# Connector_Board.net
KiCad netlist of a schematic drawn in EAGLE
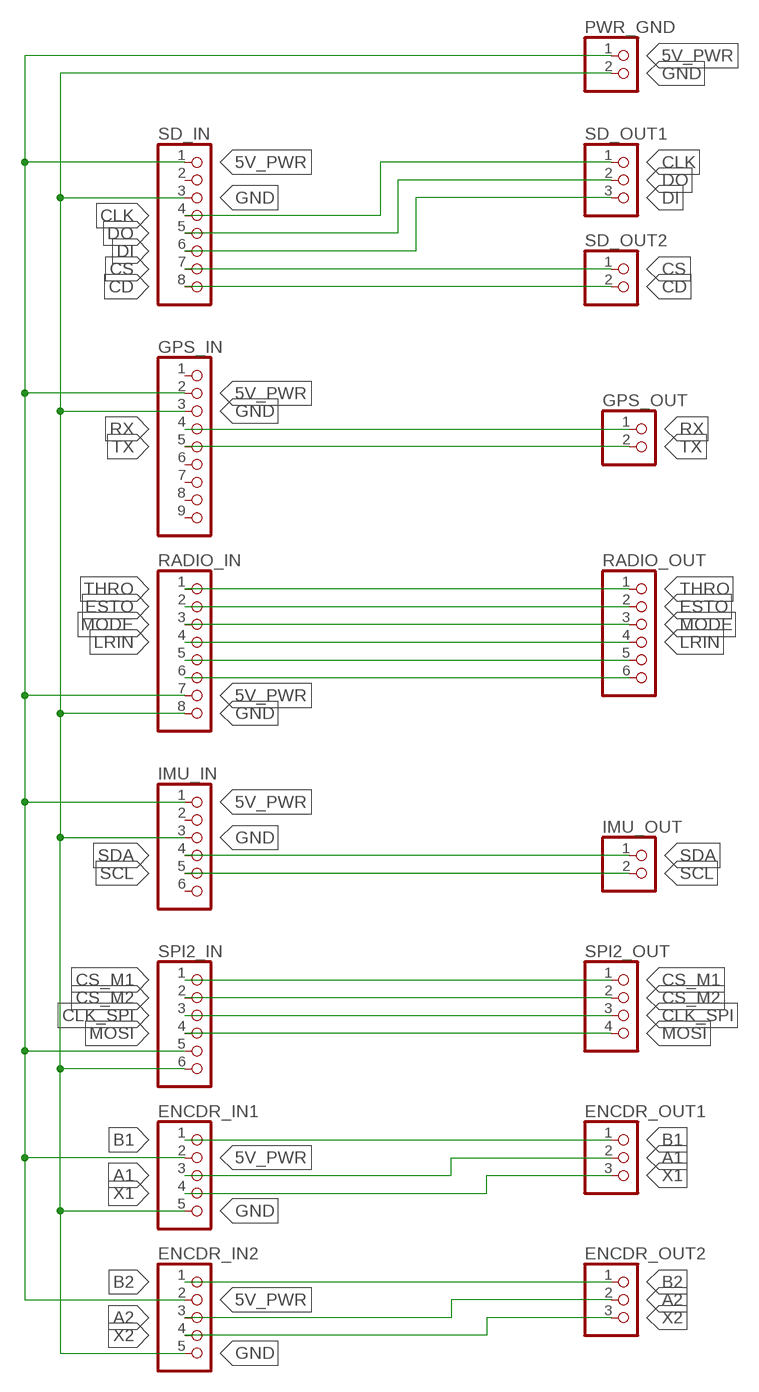
[diagram p0: schematic, sheet 1]

(export (version "E")
  (design (tool "Eeschema 10.0.6"))
  (components
    (comp (ref "ENCDR_IN1")
      (value "PINHD-1X5")
      (footprint "eagle-import:1X05")
      (libsource (lib "eagle-import") (part "PINHD-1X5"))
    )
    (comp (ref "ENCDR_IN2")
      (value "PINHD-1X5")
      (footprint "eagle-import:1X05")
      (libsource (lib "eagle-import") (part "PINHD-1X5"))
    )
    (comp (ref "ENCDR_OUT1")
      (value "PINHD-1X3")
      (footprint "eagle-import:1X03")
      (libsource (lib "eagle-import") (part "PINHD-1X3"))
    )
    (comp (ref "ENCDR_OUT2")
      (value "PINHD-1X3")
      (footprint "eagle-import:1X03")
      (libsource (lib "eagle-import") (part "PINHD-1X3"))
    )
    (comp (ref "GPS_IN")
      (value "PINHD-1X9")
      (footprint "eagle-import:1X09")
      (libsource (lib "eagle-import") (part "PINHD-1X9"))
    )
    (comp (ref "GPS_OUT")
      (value "PINHD-1X2")
      (footprint "eagle-import:1X02")
      (libsource (lib "eagle-import") (part "PINHD-1X2"))
    )
    (comp (ref "IMU_IN")
      (value "PINHD-1X6")
      (footprint "eagle-import:1X06")
      (libsource (lib "eagle-import") (part "PINHD-1X6"))
    )
    (comp (ref "IMU_OUT")
      (value "PINHD-1X2")
      (footprint "eagle-import:1X02")
      (libsource (lib "eagle-import") (part "PINHD-1X2"))
    )
    (comp (ref "PWR_GND")
      (value "PINHD-1X2")
      (footprint "eagle-import:1X02")
      (libsource (lib "eagle-import") (part "PINHD-1X2"))
    )
    (comp (ref "RADIO_IN")
      (value "PINHD-1X8")
      (footprint "eagle-import:1X08")
      (libsource (lib "eagle-import") (part "PINHD-1X8"))
    )
    (comp (ref "RADIO_OUT")
      (value "PINHD-1X6")
      (footprint "eagle-import:1X06")
      (libsource (lib "eagle-import") (part "PINHD-1X6"))
    )
    (comp (ref "SD_IN")
      (value "PINHD-1X8")
      (footprint "eagle-import:1X08")
      (libsource (lib "eagle-import") (part "PINHD-1X8"))
    )
    (comp (ref "SD_OUT1")
      (value "PINHD-1X3")
      (footprint "eagle-import:1X03")
      (libsource (lib "eagle-import") (part "PINHD-1X3"))
    )
    (comp (ref "SD_OUT2")
      (value "PINHD-1X2")
      (footprint "eagle-import:1X02")
      (libsource (lib "eagle-import") (part "PINHD-1X2"))
    )
    (comp (ref "SPI2_IN")
      (value "PINHD-1X6")
      (footprint "eagle-import:1X06")
      (libsource (lib "eagle-import") (part "PINHD-1X6"))
    )
    (comp (ref "SPI2_OUT")
      (value "PINHD-1X4")
      (footprint "eagle-import:1X04")
      (libsource (lib "eagle-import") (part "PINHD-1X4"))
    )
  )
  (nets
    (net (code "1") (name "5V_PWR") (class "Default")
      (node (ref "ENCDR_IN1") (pin "2") (pinfunction "2_2") (pintype "passive"))
      (node (ref "ENCDR_IN2") (pin "2") (pinfunction "2_2") (pintype "passive"))
      (node (ref "GPS_IN") (pin "2") (pinfunction "2_2") (pintype "passive"))
      (node (ref "IMU_IN") (pin "1") (pinfunction "1_1") (pintype "passive"))
      (node (ref "PWR_GND") (pin "1") (pinfunction "1_1") (pintype "passive"))
      (node (ref "RADIO_IN") (pin "7") (pinfunction "7_7") (pintype "passive"))
      (node (ref "SD_IN") (pin "1") (pinfunction "1_1") (pintype "passive"))
      (node (ref "SPI2_IN") (pin "5") (pinfunction "5_5") (pintype "passive"))
    )
    (net (code "2") (name "A1") (class "Default")
      (node (ref "ENCDR_IN1") (pin "3") (pinfunction "3_3") (pintype "passive"))
      (node (ref "ENCDR_OUT1") (pin "2") (pinfunction "2_2") (pintype "passive"))
    )
    (net (code "3") (name "A2") (class "Default")
      (node (ref "ENCDR_IN2") (pin "3") (pinfunction "3_3") (pintype "passive"))
      (node (ref "ENCDR_OUT2") (pin "2") (pinfunction "2_2") (pintype "passive"))
    )
    (net (code "4") (name "B1") (class "Default")
      (node (ref "ENCDR_IN1") (pin "1") (pinfunction "1_1") (pintype "passive"))
      (node (ref "ENCDR_OUT1") (pin "1") (pinfunction "1_1") (pintype "passive"))
    )
    (net (code "5") (name "B2") (class "Default")
      (node (ref "ENCDR_IN2") (pin "1") (pinfunction "1_1") (pintype "passive"))
      (node (ref "ENCDR_OUT2") (pin "1") (pinfunction "1_1") (pintype "passive"))
    )
    (net (code "6") (name "CD") (class "Default")
      (node (ref "SD_IN") (pin "8") (pinfunction "8_8") (pintype "passive"))
      (node (ref "SD_OUT2") (pin "2") (pinfunction "2_2") (pintype "passive"))
    )
    (net (code "7") (name "CLK") (class "Default")
      (node (ref "SD_IN") (pin "4") (pinfunction "4_4") (pintype "passive"))
      (node (ref "SD_OUT1") (pin "1") (pinfunction "1_1") (pintype "passive"))
    )
    (net (code "8") (name "CLK_SPI") (class "Default")
      (node (ref "SPI2_IN") (pin "3") (pinfunction "3_3") (pintype "passive"))
      (node (ref "SPI2_OUT") (pin "3") (pinfunction "3_3") (pintype "passive"))
    )
    (net (code "9") (name "CS") (class "Default")
      (node (ref "SD_IN") (pin "7") (pinfunction "7_7") (pintype "passive"))
      (node (ref "SD_OUT2") (pin "1") (pinfunction "1_1") (pintype "passive"))
    )
    (net (code "10") (name "CS_M1") (class "Default")
      (node (ref "SPI2_IN") (pin "1") (pinfunction "1_1") (pintype "passive"))
      (node (ref "SPI2_OUT") (pin "1") (pinfunction "1_1") (pintype "passive"))
    )
    (net (code "11") (name "CS_M2") (class "Default")
      (node (ref "SPI2_IN") (pin "2") (pinfunction "2_2") (pintype "passive"))
      (node (ref "SPI2_OUT") (pin "2") (pinfunction "2_2") (pintype "passive"))
    )
    (net (code "12") (name "DI") (class "Default")
      (node (ref "SD_IN") (pin "6") (pinfunction "6_6") (pintype "passive"))
      (node (ref "SD_OUT1") (pin "3") (pinfunction "3_3") (pintype "passive"))
    )
    (net (code "13") (name "DO") (class "Default")
      (node (ref "SD_IN") (pin "5") (pinfunction "5_5") (pintype "passive"))
      (node (ref "SD_OUT1") (pin "2") (pinfunction "2_2") (pintype "passive"))
    )
    (net (code "14") (name "ESTO") (class "Default")
      (node (ref "RADIO_IN") (pin "2") (pinfunction "2_2") (pintype "passive"))
      (node (ref "RADIO_OUT") (pin "2") (pinfunction "2_2") (pintype "passive"))
    )
    (net (code "15") (name "GND") (class "Default")
      (node (ref "ENCDR_IN1") (pin "5") (pinfunction "5_5") (pintype "passive"))
      (node (ref "ENCDR_IN2") (pin "5") (pinfunction "5_5") (pintype "passive"))
      (node (ref "GPS_IN") (pin "3") (pinfunction "3_3") (pintype "passive"))
      (node (ref "IMU_IN") (pin "3") (pinfunction "3_3") (pintype "passive"))
      (node (ref "PWR_GND") (pin "2") (pinfunction "2_2") (pintype "passive"))
      (node (ref "RADIO_IN") (pin "8") (pinfunction "8_8") (pintype "passive"))
      (node (ref "SD_IN") (pin "3") (pinfunction "3_3") (pintype "passive"))
      (node (ref "SPI2_IN") (pin "6") (pinfunction "6_6") (pintype "passive"))
    )
    (net (code "16") (name "LRIN") (class "Default")
      (node (ref "RADIO_IN") (pin "4") (pinfunction "4_4") (pintype "passive"))
      (node (ref "RADIO_OUT") (pin "4") (pinfunction "4_4") (pintype "passive"))
    )
    (net (code "17") (name "MODE") (class "Default")
      (node (ref "RADIO_IN") (pin "3") (pinfunction "3_3") (pintype "passive"))
      (node (ref "RADIO_OUT") (pin "3") (pinfunction "3_3") (pintype "passive"))
    )
    (net (code "18") (name "MOSI") (class "Default")
      (node (ref "SPI2_IN") (pin "4") (pinfunction "4_4") (pintype "passive"))
      (node (ref "SPI2_OUT") (pin "4") (pinfunction "4_4") (pintype "passive"))
    )
    (net (code "19") (name "Net-(RADIO_IN-Pad5)") (class "Default")
      (node (ref "RADIO_IN") (pin "5") (pinfunction "5_5") (pintype "passive"))
      (node (ref "RADIO_OUT") (pin "5") (pinfunction "5_5") (pintype "passive"))
    )
    (net (code "20") (name "Net-(RADIO_IN-Pad6)") (class "Default")
      (node (ref "RADIO_IN") (pin "6") (pinfunction "6_6") (pintype "passive"))
      (node (ref "RADIO_OUT") (pin "6") (pinfunction "6_6") (pintype "passive"))
    )
    (net (code "21") (name "RX") (class "Default")
      (node (ref "GPS_IN") (pin "4") (pinfunction "4_4") (pintype "passive"))
      (node (ref "GPS_OUT") (pin "1") (pinfunction "1_1") (pintype "passive"))
    )
    (net (code "22") (name "SCL") (class "Default")
      (node (ref "IMU_IN") (pin "5") (pinfunction "5_5") (pintype "passive"))
      (node (ref "IMU_OUT") (pin "2") (pinfunction "2_2") (pintype "passive"))
    )
    (net (code "23") (name "SDA") (class "Default")
      (node (ref "IMU_IN") (pin "4") (pinfunction "4_4") (pintype "passive"))
      (node (ref "IMU_OUT") (pin "1") (pinfunction "1_1") (pintype "passive"))
    )
    (net (code "24") (name "THRO") (class "Default")
      (node (ref "RADIO_IN") (pin "1") (pinfunction "1_1") (pintype "passive"))
      (node (ref "RADIO_OUT") (pin "1") (pinfunction "1_1") (pintype "passive"))
    )
    (net (code "25") (name "TX") (class "Default")
      (node (ref "GPS_IN") (pin "5") (pinfunction "5_5") (pintype "passive"))
      (node (ref "GPS_OUT") (pin "2") (pinfunction "2_2") (pintype "passive"))
    )
    (net (code "26") (name "X1") (class "Default")
      (node (ref "ENCDR_IN1") (pin "4") (pinfunction "4_4") (pintype "passive"))
      (node (ref "ENCDR_OUT1") (pin "3") (pinfunction "3_3") (pintype "passive"))
    )
    (net (code "27") (name "X2") (class "Default")
      (node (ref "ENCDR_IN2") (pin "4") (pinfunction "4_4") (pintype "passive"))
      (node (ref "ENCDR_OUT2") (pin "3") (pinfunction "3_3") (pintype "passive"))
    )
    (net (code "28") (name "unconnected-(GPS_IN-Pad1)") (class "Default")
      (node (ref "GPS_IN") (pin "1") (pinfunction "1_1") (pintype "passive"))
    )
    (net (code "29") (name "unconnected-(GPS_IN-Pad6)") (class "Default")
      (node (ref "GPS_IN") (pin "6") (pinfunction "6_6") (pintype "passive"))
    )
    (net (code "30") (name "unconnected-(GPS_IN-Pad7)") (class "Default")
      (node (ref "GPS_IN") (pin "7") (pinfunction "7_7") (pintype "passive"))
    )
    (net (code "31") (name "unconnected-(GPS_IN-Pad8)") (class "Default")
      (node (ref "GPS_IN") (pin "8") (pinfunction "8_8") (pintype "passive"))
    )
    (net (code "32") (name "unconnected-(GPS_IN-Pad9)") (class "Default")
      (node (ref "GPS_IN") (pin "9") (pinfunction "9_9") (pintype "passive"))
    )
    (net (code "33") (name "unconnected-(IMU_IN-Pad2)") (class "Default")
      (node (ref "IMU_IN") (pin "2") (pinfunction "2_2") (pintype "passive"))
    )
    (net (code "34") (name "unconnected-(IMU_IN-Pad6)") (class "Default")
      (node (ref "IMU_IN") (pin "6") (pinfunction "6_6") (pintype "passive"))
    )
    (net (code "35") (name "unconnected-(SD_IN-Pad2)") (class "Default")
      (node (ref "SD_IN") (pin "2") (pinfunction "2_2") (pintype "passive"))
    )
  )
)
